# pro-micro-screw-terminal-v1_1.net
KiCad netlist of a schematic drawn in EAGLE
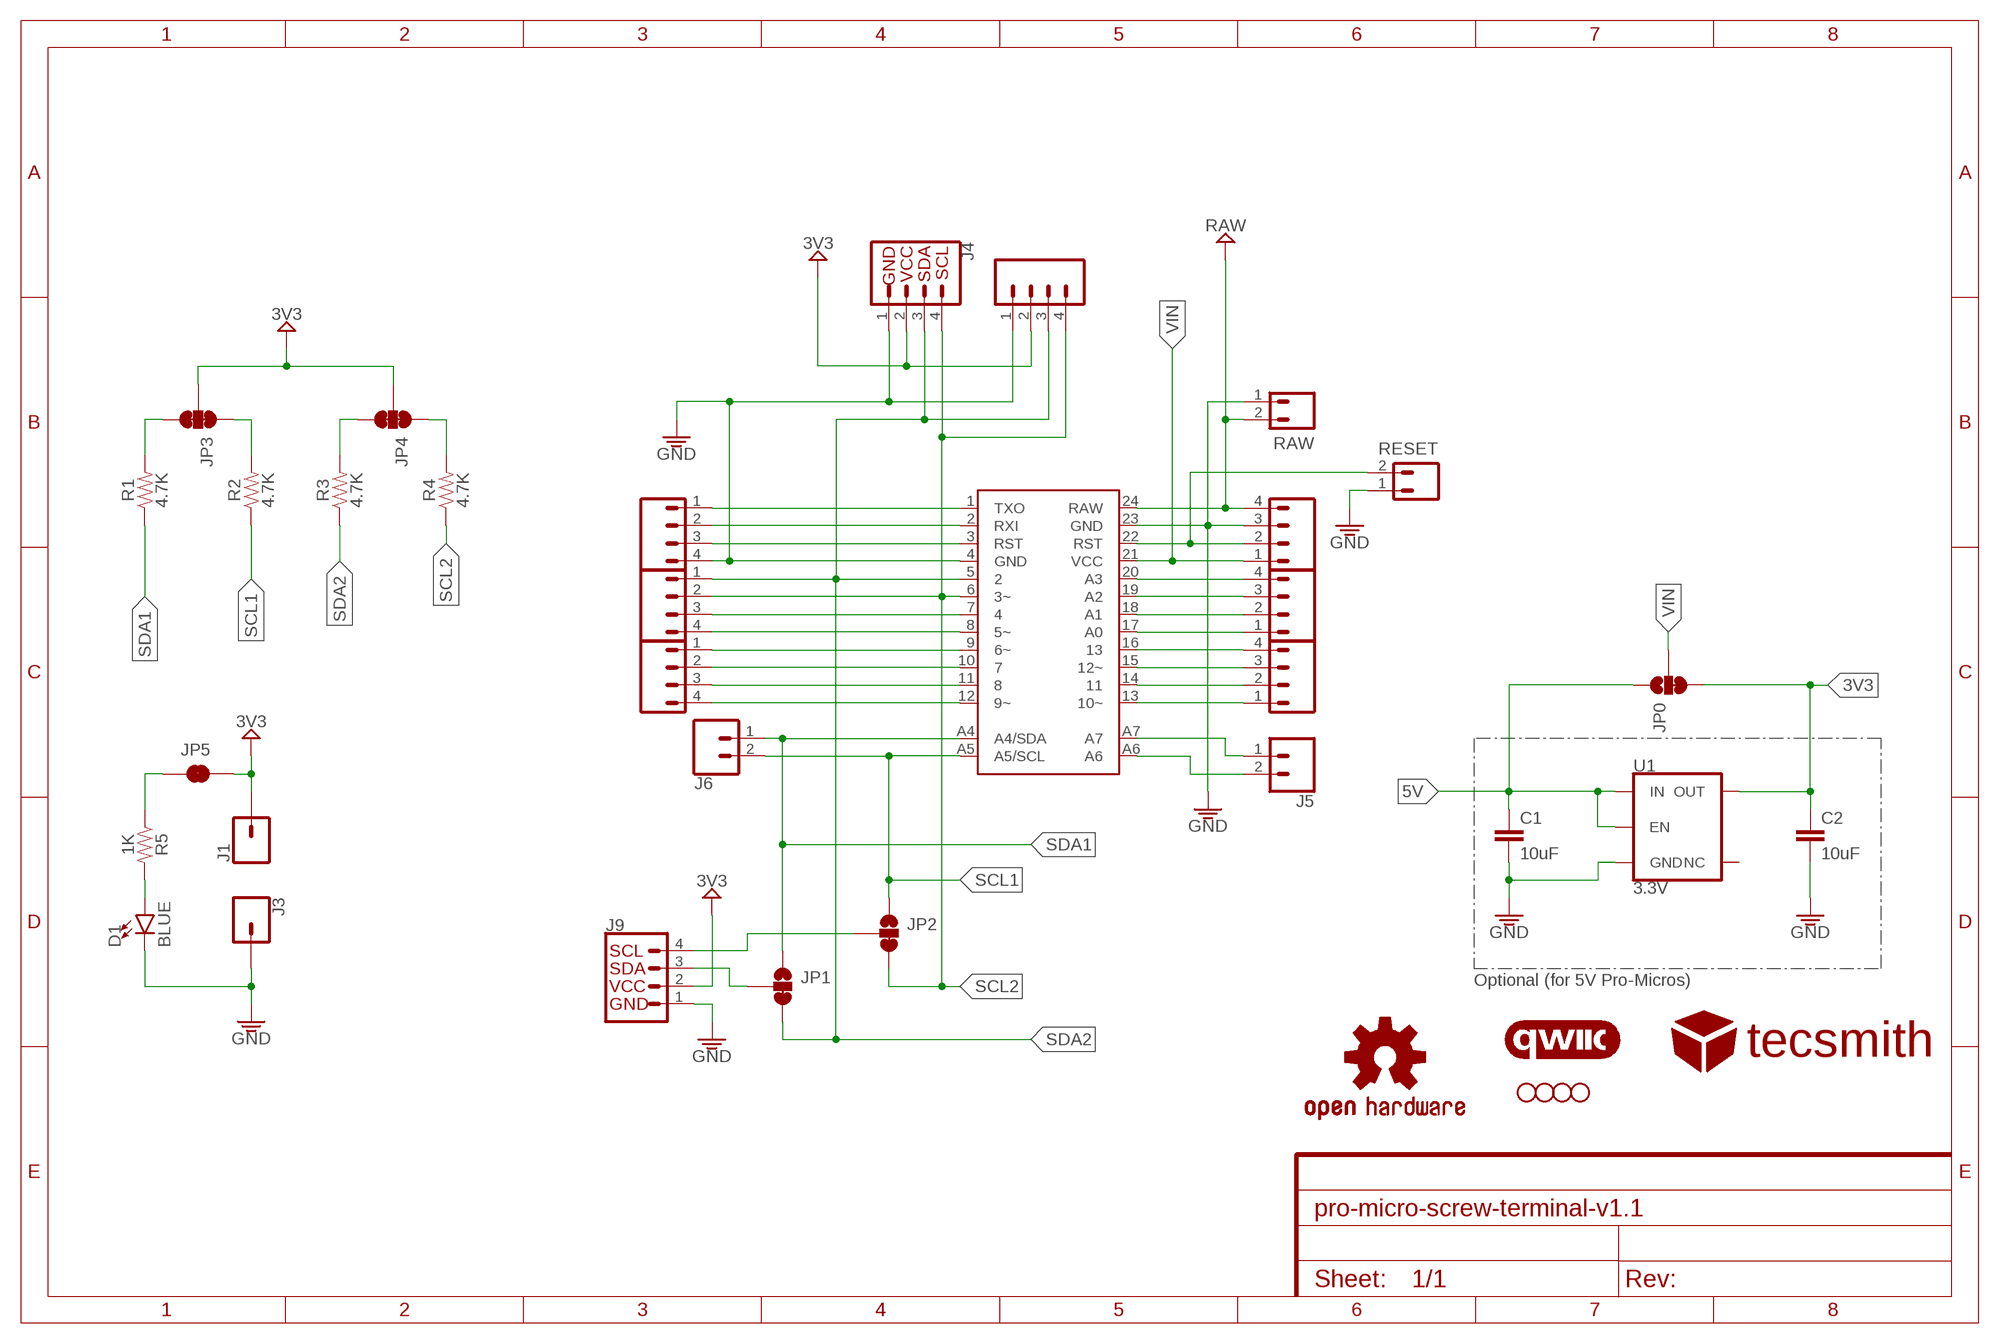
[diagram p0: schematic, sheet 1]

(export (version "E")
  (design (tool "Eeschema 10.0.6"))
  (components
    (comp (ref "B1")
      (value "ARDUINO_PRO_MININO_FTDI")
      (footprint "eagle-import:ARDUINO_PRO_MINI")
      (libsource (lib "eagle-import") (part "ARDUINO_PRO_MININO_FTDI"))
    )
    (comp (ref "C1")
      (value "10uF")
      (footprint "eagle-import:0603")
      (libsource (lib "eagle-import") (part "10UF-0603-6.3V-20%"))
    )
    (comp (ref "C2")
      (value "10uF")
      (footprint "eagle-import:0603")
      (libsource (lib "eagle-import") (part "10UF-0603-6.3V-20%"))
    )
    (comp (ref "D1")
      (value "BLUE")
      (footprint "eagle-import:LED-0603")
      (libsource (lib "eagle-import") (part "LED-BLUE0603"))
    )
    (comp (ref "H1")
      (value "STAND-OFF")
      (footprint "eagle-import:STAND-OFF")
      (libsource (lib "eagle-import") (part "STAND-OFF"))
    )
    (comp (ref "H2")
      (value "STAND-OFF")
      (footprint "eagle-import:STAND-OFF")
      (libsource (lib "eagle-import") (part "STAND-OFF"))
    )
    (comp (ref "H5")
      (value "STAND-OFF")
      (footprint "eagle-import:STAND-OFF")
      (libsource (lib "eagle-import") (part "STAND-OFF"))
    )
    (comp (ref "H6")
      (value "STAND-OFF")
      (footprint "eagle-import:STAND-OFF")
      (libsource (lib "eagle-import") (part "STAND-OFF"))
    )
    (comp (ref "J1")
      (value "CONN_01PTH_NO_SILK_YES_STOP")
      (footprint "eagle-import:1X01_NO_SILK")
      (libsource (lib "eagle-import") (part "CONN_01PTH_NO_SILK_YES_STOP"))
    )
    (comp (ref "J2")
      (value "CONN_04PTH")
      (footprint "eagle-import:1X04")
      (libsource (lib "eagle-import") (part "CONN_04PTH"))
    )
    (comp (ref "J3")
      (value "CONN_01PTH_NO_SILK_YES_STOP")
      (footprint "eagle-import:1X01_NO_SILK")
      (libsource (lib "eagle-import") (part "CONN_01PTH_NO_SILK_YES_STOP"))
    )
    (comp (ref "J4")
      (value "QWIIC_RIGHT_ANGLE")
      (footprint "eagle-import:JST04_1MM_RA")
      (libsource (lib "eagle-import") (part "QWIIC_CONNECTORJS-1MM"))
    )
    (comp (ref "J5")
      (value "CONN_02")
      (footprint "eagle-import:1X02")
      (libsource (lib "eagle-import") (part "CONN_02"))
    )
    (comp (ref "J6")
      (value "CONN_02")
      (footprint "eagle-import:1X02")
      (libsource (lib "eagle-import") (part "CONN_02"))
    )
    (comp (ref "J9")
      (value "QWIIC_RIGHT_ANGLE")
      (footprint "eagle-import:JST04_1MM_RA")
      (libsource (lib "eagle-import") (part "QWIIC_CONNECTORJS-1MM"))
    )
    (comp (ref "JP0")
      (value "JUMPER-SMT_3_1-NC_TRACE_SILK")
      (footprint "eagle-import:SMT-JUMPER_3_1-NC_TRACE_SILK")
      (libsource (lib "eagle-import") (part "JUMPER-SMT_3_1-NC_TRACE_SILK"))
    )
    (comp (ref "JP1")
      (value "JUMPER-SMT_3_1-NC_TRACE_SILK")
      (footprint "eagle-import:SMT-JUMPER_3_1-NC_TRACE_SILK")
      (libsource (lib "eagle-import") (part "JUMPER-SMT_3_1-NC_TRACE_SILK"))
    )
    (comp (ref "JP2")
      (value "JUMPER-SMT_3_1-NC_TRACE_SILK")
      (footprint "eagle-import:SMT-JUMPER_3_1-NC_TRACE_SILK")
      (libsource (lib "eagle-import") (part "JUMPER-SMT_3_1-NC_TRACE_SILK"))
    )
    (comp (ref "JP3")
      (value "JUMPER-SMT_3_2-NC_TRACE_SILK")
      (footprint "eagle-import:SMT-JUMPER_3_2-NC_TRACE_SILK")
      (libsource (lib "eagle-import") (part "JUMPER-SMT_3_2-NC_TRACE_SILK"))
    )
    (comp (ref "JP4")
      (value "JUMPER-SMT_3_2-NC_TRACE_SILK")
      (footprint "eagle-import:SMT-JUMPER_3_2-NC_TRACE_SILK")
      (libsource (lib "eagle-import") (part "JUMPER-SMT_3_2-NC_TRACE_SILK"))
    )
    (comp (ref "JP5")
      (value "JUMPER-SMT_2_NC_TRACE_SILK")
      (footprint "eagle-import:SMT-JUMPER_2_NC_TRACE_SILK")
      (libsource (lib "eagle-import") (part "JUMPER-SMT_2_NC_TRACE_SILK"))
    )
    (comp (ref "LOGO1")
      (value "OSHW-LOGOS")
      (footprint "eagle-import:OSHW-LOGO-S")
      (libsource (lib "eagle-import") (part "OSHW-LOGOS"))
    )
    (comp (ref "LOGO2")
      (value "QWIIC_LOGO_6MM")
      (footprint "eagle-import:QWIIC_6MM")
      (libsource (lib "eagle-import") (part "QWIIC_LOGO_6MM"))
    )
    (comp (ref "R1")
      (value "4.7K")
      (footprint "eagle-import:0805")
      (libsource (lib "eagle-import") (part "RESISTOR0805"))
    )
    (comp (ref "R2")
      (value "4.7K")
      (footprint "eagle-import:0805")
      (libsource (lib "eagle-import") (part "RESISTOR0805"))
    )
    (comp (ref "R3")
      (value "4.7K")
      (footprint "eagle-import:0805")
      (libsource (lib "eagle-import") (part "RESISTOR0805"))
    )
    (comp (ref "R4")
      (value "4.7K")
      (footprint "eagle-import:0805")
      (libsource (lib "eagle-import") (part "RESISTOR0805"))
    )
    (comp (ref "R5")
      (value "1K")
      (footprint "eagle-import:0603")
      (libsource (lib "eagle-import") (part "330OHM-0603-1/10W-1%"))
    )
    (comp (ref "RAW")
      (value "CON_02SCREW")
      (footprint "eagle-import:WURTH_2431_3.5MM_2X_SCREW")
      (libsource (lib "eagle-import") (part "CON_02SCREW"))
    )
    (comp (ref "RESET")
      (value "JST-PH-2NS")
      (footprint "eagle-import:JST-PH2-NO-SILK")
      (libsource (lib "eagle-import") (part "JST-PH-2NS"))
    )
    (comp (ref "U$1")
      (value "CON_04SCREW")
      (footprint "eagle-import:WURTH_2431_3.5MM_4X_SCREW")
      (libsource (lib "eagle-import") (part "CON_04SCREW"))
    )
    (comp (ref "U$2")
      (value "CON_04SCREW")
      (footprint "eagle-import:WURTH_2431_3.5MM_4X_SCREW")
      (libsource (lib "eagle-import") (part "CON_04SCREW"))
    )
    (comp (ref "U$3")
      (value "CON_04SCREW")
      (footprint "eagle-import:WURTH_2431_3.5MM_4X_SCREW")
      (libsource (lib "eagle-import") (part "CON_04SCREW"))
    )
    (comp (ref "U$4")
      (value "CON_04SCREW")
      (footprint "eagle-import:WURTH_2431_3.5MM_4X_SCREW")
      (libsource (lib "eagle-import") (part "CON_04SCREW"))
    )
    (comp (ref "U$5")
      (value "CON_04SCREW")
      (footprint "eagle-import:WURTH_2431_3.5MM_4X_SCREW")
      (libsource (lib "eagle-import") (part "CON_04SCREW"))
    )
    (comp (ref "U$6")
      (value "CON_04SCREW")
      (footprint "eagle-import:WURTH_2431_3.5MM_4X_SCREW")
      (libsource (lib "eagle-import") (part "CON_04SCREW"))
    )
    (comp (ref "U$9")
      (value "TECSMITH-LOGO")
      (footprint "eagle-import:TECSMITH-LOGO")
      (libsource (lib "eagle-import") (part "TECSMITH-LOGO"))
    )
    (comp (ref "U1")
      (value "3.3V")
      (footprint "eagle-import:SOT23-5")
      (libsource (lib "eagle-import") (part "V_REG_AP2112K-3.3V"))
    )
  )
  (nets
    (net (code "1") (name "3V3") (class "Default")
      (node (ref "C2") (pin "1") (pinfunction "1_1") (pintype "passive"))
      (node (ref "J1") (pin "1") (pinfunction "1_1") (pintype "passive"))
      (node (ref "J2") (pin "2") (pinfunction "2_2") (pintype "passive"))
      (node (ref "J4") (pin "2") (pinfunction "2_2") (pintype "power_in"))
      (node (ref "J9") (pin "2") (pinfunction "2_2") (pintype "power_in"))
      (node (ref "JP0") (pin "3") (pinfunction "3_3") (pintype "passive"))
      (node (ref "JP3") (pin "2") (pinfunction "2_2") (pintype "passive"))
      (node (ref "JP4") (pin "2") (pinfunction "2_2") (pintype "passive"))
      (node (ref "JP5") (pin "2") (pinfunction "2_2") (pintype "passive"))
      (node (ref "U1") (pin "5") (pinfunction "OUT_5") (pintype "passive"))
    )
    (net (code "2") (name "5V") (class "Default")
      (node (ref "C1") (pin "1") (pinfunction "1_1") (pintype "passive"))
      (node (ref "JP0") (pin "1") (pinfunction "1_1") (pintype "passive"))
      (node (ref "U1") (pin "1") (pinfunction "IN_1") (pintype "input"))
      (node (ref "U1") (pin "3") (pinfunction "EN_3") (pintype "input"))
    )
    (net (code "3") (name "GND") (class "Default")
      (node (ref "B1") (pin "23") (pinfunction "GND_23") (pintype "power_in"))
      (node (ref "B1") (pin "4") (pinfunction "GND_4") (pintype "power_in"))
      (node (ref "C1") (pin "2") (pinfunction "2_2") (pintype "passive"))
      (node (ref "C2") (pin "2") (pinfunction "2_2") (pintype "passive"))
      (node (ref "D1") (pin "C") (pinfunction "C_C") (pintype "passive"))
      (node (ref "J2") (pin "1") (pinfunction "1_1") (pintype "passive"))
      (node (ref "J3") (pin "1") (pinfunction "1_1") (pintype "passive"))
      (node (ref "J4") (pin "1") (pinfunction "1_1") (pintype "power_in"))
      (node (ref "J9") (pin "1") (pinfunction "1_1") (pintype "power_in"))
      (node (ref "RAW") (pin "1") (pinfunction "1_1") (pintype "passive"))
      (node (ref "RESET") (pin "1") (pinfunction "1_1") (pintype "passive"))
      (node (ref "U$1") (pin "4") (pinfunction "4_4") (pintype "passive"))
      (node (ref "U$6") (pin "3") (pinfunction "3_3") (pintype "passive"))
      (node (ref "U1") (pin "2") (pinfunction "GND_2") (pintype "input"))
    )
    (net (code "4") (name "Net-(B1-4)") (class "Default")
      (node (ref "B1") (pin "7") (pinfunction "4_7") (pintype "bidirectional"))
      (node (ref "U$2") (pin "3") (pinfunction "3_3") (pintype "passive"))
    )
    (net (code "5") (name "Net-(B1-5~{})") (class "Default")
      (node (ref "B1") (pin "8") (pinfunction "5~{}_8") (pintype "bidirectional"))
      (node (ref "U$2") (pin "4") (pinfunction "4_4") (pintype "passive"))
    )
    (net (code "6") (name "Net-(B1-6~{})") (class "Default")
      (node (ref "B1") (pin "9") (pinfunction "6~{}_9") (pintype "bidirectional"))
      (node (ref "U$3") (pin "1") (pinfunction "1_1") (pintype "passive"))
    )
    (net (code "7") (name "Net-(B1-7)") (class "Default")
      (node (ref "B1") (pin "10") (pinfunction "7_10") (pintype "bidirectional"))
      (node (ref "U$3") (pin "2") (pinfunction "2_2") (pintype "passive"))
    )
    (net (code "8") (name "Net-(B1-8)") (class "Default")
      (node (ref "B1") (pin "11") (pinfunction "8_11") (pintype "bidirectional"))
      (node (ref "U$3") (pin "3") (pinfunction "3_3") (pintype "passive"))
    )
    (net (code "9") (name "Net-(B1-9~{})") (class "Default")
      (node (ref "B1") (pin "12") (pinfunction "9~{}_12") (pintype "bidirectional"))
      (node (ref "U$3") (pin "4") (pinfunction "4_4") (pintype "passive"))
    )
    (net (code "10") (name "Net-(B1-10~{})") (class "Default")
      (node (ref "B1") (pin "13") (pinfunction "10~{}_13") (pintype "bidirectional"))
      (node (ref "U$4") (pin "1") (pinfunction "1_1") (pintype "passive"))
    )
    (net (code "11") (name "Net-(B1-11)") (class "Default")
      (node (ref "B1") (pin "14") (pinfunction "11_14") (pintype "bidirectional"))
      (node (ref "U$4") (pin "2") (pinfunction "2_2") (pintype "passive"))
    )
    (net (code "12") (name "Net-(B1-12~{})") (class "Default")
      (node (ref "B1") (pin "15") (pinfunction "12~{}_15") (pintype "bidirectional"))
      (node (ref "U$4") (pin "3") (pinfunction "3_3") (pintype "passive"))
    )
    (net (code "13") (name "Net-(B1-13)") (class "Default")
      (node (ref "B1") (pin "16") (pinfunction "13_16") (pintype "bidirectional"))
      (node (ref "U$4") (pin "4") (pinfunction "4_4") (pintype "passive"))
    )
    (net (code "14") (name "Net-(B1-A0)") (class "Default")
      (node (ref "B1") (pin "17") (pinfunction "A0_17") (pintype "bidirectional"))
      (node (ref "U$5") (pin "1") (pinfunction "1_1") (pintype "passive"))
    )
    (net (code "15") (name "Net-(B1-A1)") (class "Default")
      (node (ref "B1") (pin "18") (pinfunction "A1_18") (pintype "bidirectional"))
      (node (ref "U$5") (pin "2") (pinfunction "2_2") (pintype "passive"))
    )
    (net (code "16") (name "Net-(B1-A2)") (class "Default")
      (node (ref "B1") (pin "19") (pinfunction "A2_19") (pintype "bidirectional"))
      (node (ref "U$5") (pin "3") (pinfunction "3_3") (pintype "passive"))
    )
    (net (code "17") (name "Net-(B1-A3)") (class "Default")
      (node (ref "B1") (pin "20") (pinfunction "A3_20") (pintype "bidirectional"))
      (node (ref "U$5") (pin "4") (pinfunction "4_4") (pintype "passive"))
    )
    (net (code "18") (name "Net-(B1-PadA6)") (class "Default")
      (node (ref "B1") (pin "A6") (pinfunction "A6_A6") (pintype "bidirectional"))
      (node (ref "J5") (pin "2") (pinfunction "2_2") (pintype "passive"))
    )
    (net (code "19") (name "Net-(B1-PadA7)") (class "Default")
      (node (ref "B1") (pin "A7") (pinfunction "A7_A7") (pintype "bidirectional"))
      (node (ref "J5") (pin "1") (pinfunction "1_1") (pintype "passive"))
    )
    (net (code "20") (name "Net-(B1-RST-Pad3)") (class "Default")
      (node (ref "B1") (pin "3") (pinfunction "RST_3") (pintype "bidirectional"))
      (node (ref "U$1") (pin "3") (pinfunction "3_3") (pintype "passive"))
    )
    (net (code "21") (name "Net-(B1-RST-Pad22)") (class "Default")
      (node (ref "B1") (pin "22") (pinfunction "RST_22") (pintype "bidirectional"))
      (node (ref "RESET") (pin "2") (pinfunction "2_2") (pintype "passive"))
      (node (ref "U$6") (pin "2") (pinfunction "2_2") (pintype "passive"))
    )
    (net (code "22") (name "Net-(B1-RXI)") (class "Default")
      (node (ref "B1") (pin "2") (pinfunction "RXI_2") (pintype "bidirectional"))
      (node (ref "U$1") (pin "2") (pinfunction "2_2") (pintype "passive"))
    )
    (net (code "23") (name "Net-(B1-TXO)") (class "Default")
      (node (ref "B1") (pin "1") (pinfunction "TXO_1") (pintype "bidirectional"))
      (node (ref "U$1") (pin "1") (pinfunction "1_1") (pintype "passive"))
    )
    (net (code "24") (name "Net-(D1-PadA)") (class "Default")
      (node (ref "D1") (pin "A") (pinfunction "A_A") (pintype "passive"))
      (node (ref "R5") (pin "2") (pinfunction "2_2") (pintype "passive"))
    )
    (net (code "25") (name "Net-(J9-Pad3)") (class "Default")
      (node (ref "J9") (pin "3") (pinfunction "3_3") (pintype "passive"))
      (node (ref "JP1") (pin "2") (pinfunction "2_2") (pintype "passive"))
    )
    (net (code "26") (name "Net-(J9-Pad4)") (class "Default")
      (node (ref "J9") (pin "4") (pinfunction "4_4") (pintype "passive"))
      (node (ref "JP2") (pin "2") (pinfunction "2_2") (pintype "passive"))
    )
    (net (code "27") (name "Net-(JP3-Pad1)") (class "Default")
      (node (ref "JP3") (pin "1") (pinfunction "1_1") (pintype "passive"))
      (node (ref "R2") (pin "2") (pinfunction "2_2") (pintype "passive"))
    )
    (net (code "28") (name "Net-(JP3-Pad3)") (class "Default")
      (node (ref "JP3") (pin "3") (pinfunction "3_3") (pintype "passive"))
      (node (ref "R1") (pin "2") (pinfunction "2_2") (pintype "passive"))
    )
    (net (code "29") (name "Net-(JP4-Pad1)") (class "Default")
      (node (ref "JP4") (pin "1") (pinfunction "1_1") (pintype "passive"))
      (node (ref "R4") (pin "2") (pinfunction "2_2") (pintype "passive"))
    )
    (net (code "30") (name "Net-(JP4-Pad3)") (class "Default")
      (node (ref "JP4") (pin "3") (pinfunction "3_3") (pintype "passive"))
      (node (ref "R3") (pin "2") (pinfunction "2_2") (pintype "passive"))
    )
    (net (code "31") (name "Net-(JP5-Pad1)") (class "Default")
      (node (ref "JP5") (pin "1") (pinfunction "1_1") (pintype "passive"))
      (node (ref "R5") (pin "1") (pinfunction "1_1") (pintype "passive"))
    )
    (net (code "32") (name "RAW") (class "Default")
      (node (ref "B1") (pin "24") (pinfunction "RAW_24") (pintype "power_in"))
      (node (ref "RAW") (pin "2") (pinfunction "2_2") (pintype "passive"))
      (node (ref "U$6") (pin "4") (pinfunction "4_4") (pintype "passive"))
    )
    (net (code "33") (name "SCL1") (class "Default")
      (node (ref "B1") (pin "A5") (pinfunction "A5/SCL_A5") (pintype "bidirectional"))
      (node (ref "J6") (pin "2") (pinfunction "2_2") (pintype "passive"))
      (node (ref "JP2") (pin "1") (pinfunction "1_1") (pintype "passive"))
      (node (ref "R2") (pin "1") (pinfunction "1_1") (pintype "passive"))
    )
    (net (code "34") (name "SCL2") (class "Default")
      (node (ref "B1") (pin "6") (pinfunction "3~{}_6") (pintype "bidirectional"))
      (node (ref "J2") (pin "4") (pinfunction "4_4") (pintype "passive"))
      (node (ref "J4") (pin "4") (pinfunction "4_4") (pintype "passive"))
      (node (ref "JP2") (pin "3") (pinfunction "3_3") (pintype "passive"))
      (node (ref "R4") (pin "1") (pinfunction "1_1") (pintype "passive"))
      (node (ref "U$2") (pin "2") (pinfunction "2_2") (pintype "passive"))
    )
    (net (code "35") (name "SDA1") (class "Default")
      (node (ref "B1") (pin "A4") (pinfunction "A4/SDA_A4") (pintype "bidirectional"))
      (node (ref "J6") (pin "1") (pinfunction "1_1") (pintype "passive"))
      (node (ref "JP1") (pin "1") (pinfunction "1_1") (pintype "passive"))
      (node (ref "R1") (pin "1") (pinfunction "1_1") (pintype "passive"))
    )
    (net (code "36") (name "SDA2") (class "Default")
      (node (ref "B1") (pin "5") (pinfunction "2_5") (pintype "bidirectional"))
      (node (ref "J2") (pin "3") (pinfunction "3_3") (pintype "passive"))
      (node (ref "J4") (pin "3") (pinfunction "3_3") (pintype "passive"))
      (node (ref "JP1") (pin "3") (pinfunction "3_3") (pintype "passive"))
      (node (ref "R3") (pin "1") (pinfunction "1_1") (pintype "passive"))
      (node (ref "U$2") (pin "1") (pinfunction "1_1") (pintype "passive"))
    )
    (net (code "37") (name "VIN") (class "Default")
      (node (ref "B1") (pin "21") (pinfunction "VCC_21") (pintype "power_in"))
      (node (ref "JP0") (pin "2") (pinfunction "2_2") (pintype "passive"))
      (node (ref "U$6") (pin "1") (pinfunction "1_1") (pintype "passive"))
    )
    (net (code "38") (name "unconnected-(U1-NC-Pad4)") (class "Default")
      (node (ref "U1") (pin "4") (pinfunction "NC_4") (pintype "no_connect"))
    )
  )
)
